# Needler_Rev_1_00.net
KiCad netlist of a schematic drawn in EAGLE
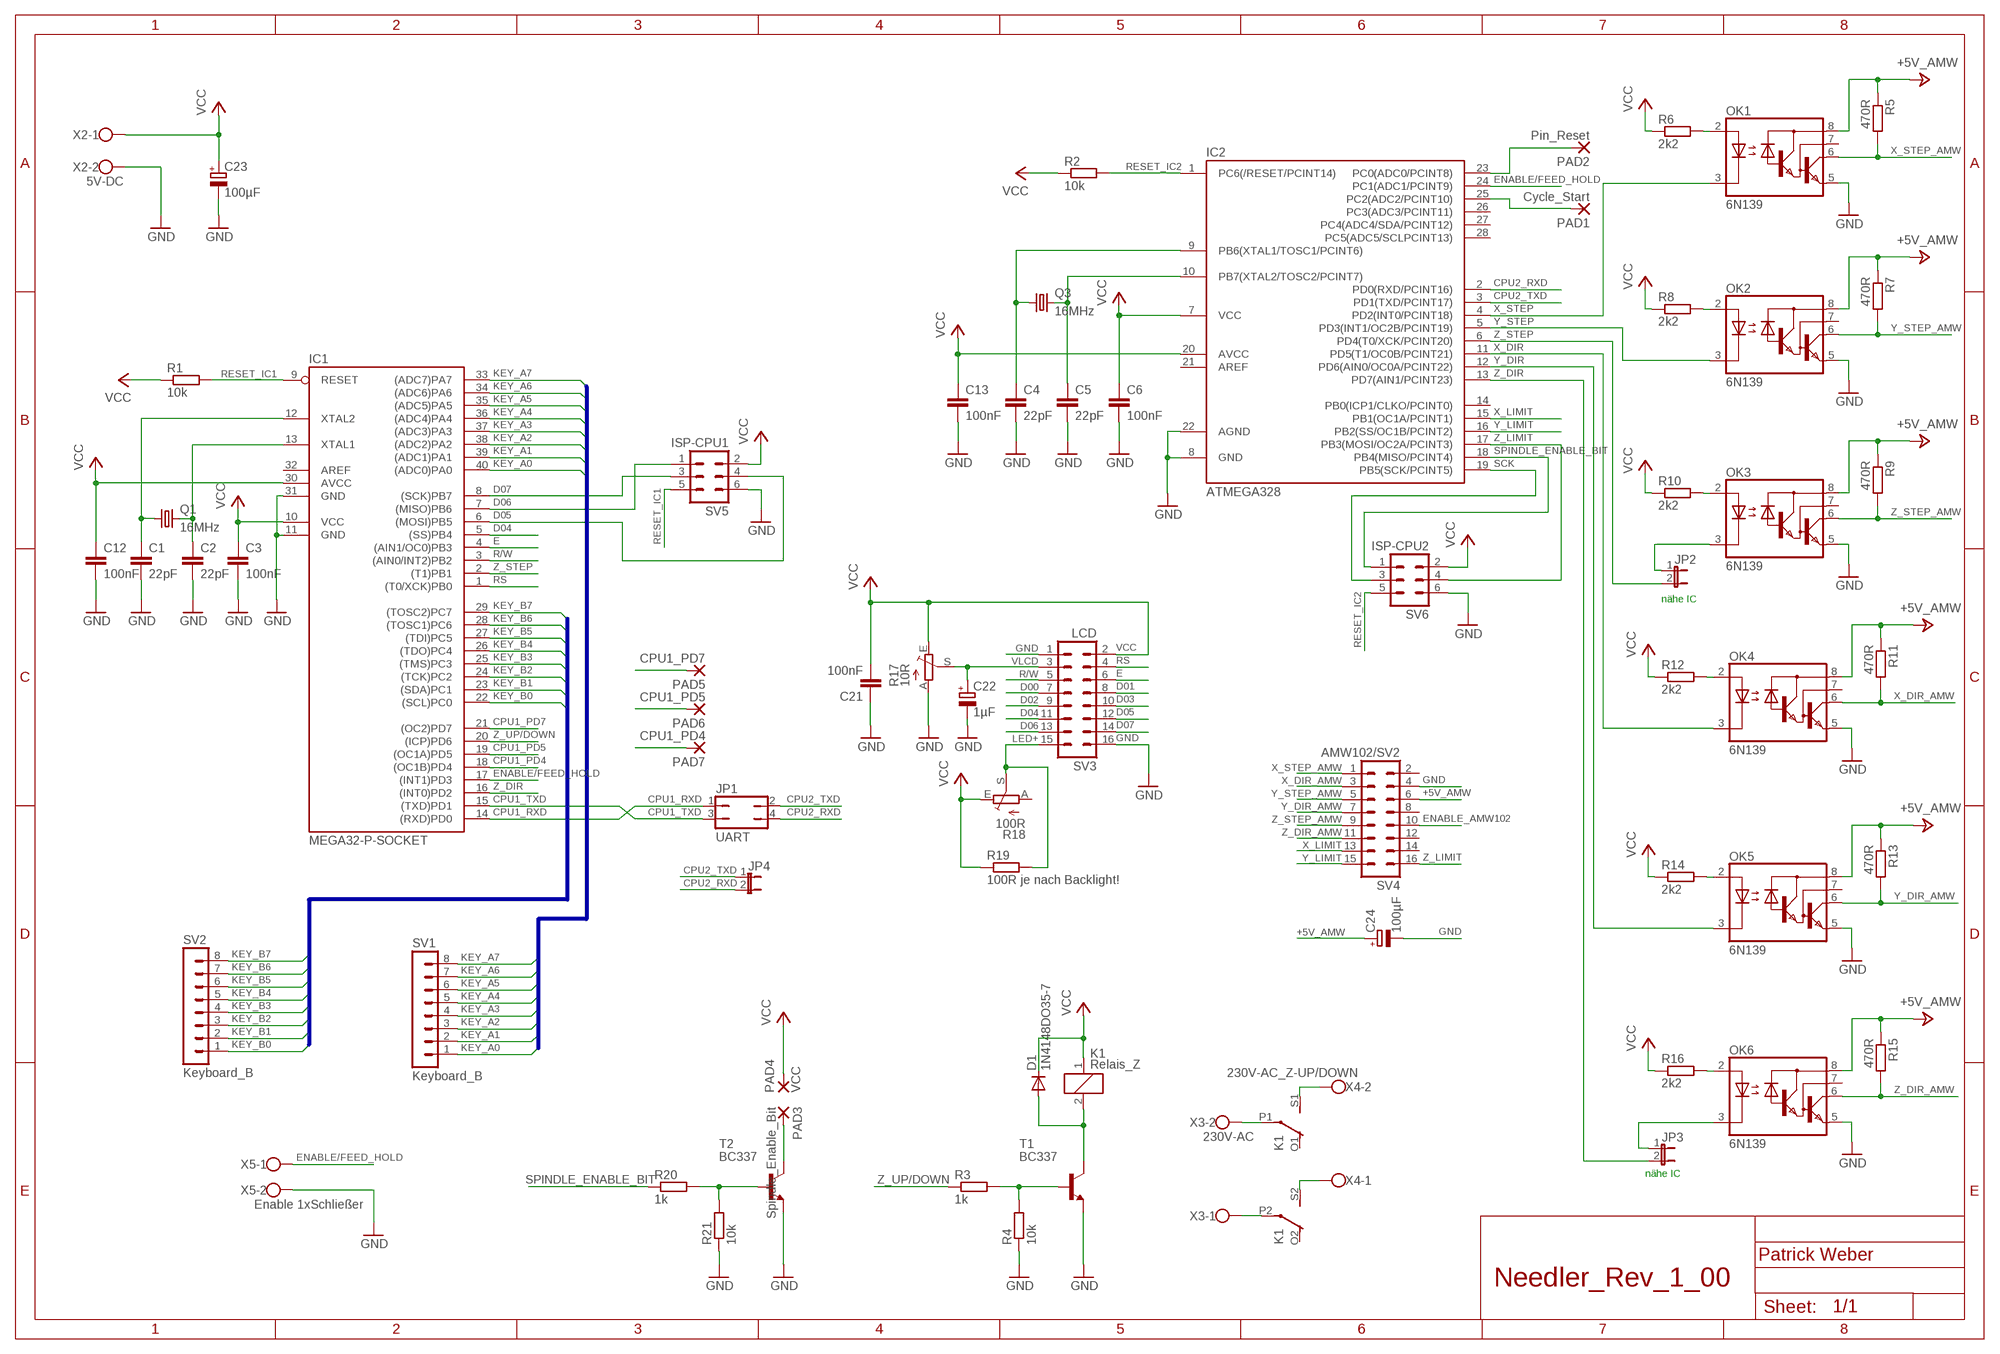
[diagram p0: schematic, sheet 1]

(export (version "E")
  (design (tool "Eeschema 10.0.6"))
  (components
    (comp (ref "C1")
      (value "22pF")
      (footprint "eagle-import:C1206")
      (libsource (lib "eagle-import") (part "C-EUC1206"))
    )
    (comp (ref "C2")
      (value "22pF")
      (footprint "eagle-import:C1206")
      (libsource (lib "eagle-import") (part "C-EUC1206"))
    )
    (comp (ref "C3")
      (value "100nF")
      (footprint "eagle-import:C050-024X044")
      (libsource (lib "eagle-import") (part "C-EU050-024X044"))
    )
    (comp (ref "C4")
      (value "22pF")
      (footprint "eagle-import:C1206")
      (libsource (lib "eagle-import") (part "C-EUC1206"))
    )
    (comp (ref "C5")
      (value "22pF")
      (footprint "eagle-import:C1206")
      (libsource (lib "eagle-import") (part "C-EUC1206"))
    )
    (comp (ref "C6")
      (value "100nF")
      (footprint "eagle-import:C050-024X044")
      (libsource (lib "eagle-import") (part "C-EU050-024X044"))
    )
    (comp (ref "C12")
      (value "100nF")
      (footprint "eagle-import:C050-024X044")
      (libsource (lib "eagle-import") (part "C-EU050-024X044"))
    )
    (comp (ref "C13")
      (value "100nF")
      (footprint "eagle-import:C050-024X044")
      (libsource (lib "eagle-import") (part "C-EU050-024X044"))
    )
    (comp (ref "C21")
      (value "100nF")
      (footprint "eagle-import:C050-024X044")
      (libsource (lib "eagle-import") (part "C-EU050-024X044"))
    )
    (comp (ref "C22")
      (value "1µF")
      (footprint "eagle-import:E2,5-6")
      (libsource (lib "eagle-import") (part "CPOL-EUE2.5-6"))
    )
    (comp (ref "C23")
      (value "100µF")
      (footprint "eagle-import:E2,5-6")
      (libsource (lib "eagle-import") (part "CPOL-EUE2.5-6"))
    )
    (comp (ref "C24")
      (value "100µF")
      (footprint "eagle-import:E2,5-6")
      (libsource (lib "eagle-import") (part "CPOL-EUE2.5-6"))
    )
    (comp (ref "D1")
      (value "1N4148DO35-7")
      (footprint "eagle-import:DO35-7")
      (libsource (lib "eagle-import") (part "1N4148DO35-7"))
    )
    (comp (ref "IC1")
      (value "MEGA32-P-SOCKET")
      (footprint "eagle-import:DIL40-SOCKET")
      (libsource (lib "eagle-import") (part "MEGA32-P-SOCKET"))
    )
    (comp (ref "IC2")
      (value "ATMEGA328")
      (footprint "eagle-import:DIL28-3")
      (libsource (lib "eagle-import") (part "MEGA48/88/168-PU"))
    )
    (comp (ref "JP1")
      (value "UART")
      (footprint "eagle-import:JP2Q")
      (libsource (lib "eagle-import") (part "JP2Q"))
    )
    (comp (ref "JP2")
      (value "JP1E")
      (footprint "eagle-import:JP1")
      (libsource (lib "eagle-import") (part "JP1E"))
    )
    (comp (ref "JP3")
      (value "JP1E")
      (footprint "eagle-import:JP1")
      (libsource (lib "eagle-import") (part "JP1E"))
    )
    (comp (ref "JP4")
      (value "JP1E")
      (footprint "eagle-import:JP1")
      (libsource (lib "eagle-import") (part "JP1E"))
    )
    (comp (ref "K1")
      (value "Relais_Z")
      (footprint "eagle-import:HF118F")
      (libsource (lib "eagle-import") (part "G2R2HF118F"))
    )
    (comp (ref "OK1")
      (value "6N139")
      (footprint "eagle-import:SO8-GW300")
      (libsource (lib "eagle-import") (part "6N138"))
    )
    (comp (ref "OK2")
      (value "6N139")
      (footprint "eagle-import:SO8-GW300")
      (libsource (lib "eagle-import") (part "6N138"))
    )
    (comp (ref "OK3")
      (value "6N139")
      (footprint "eagle-import:SO8-GW300")
      (libsource (lib "eagle-import") (part "6N138"))
    )
    (comp (ref "OK4")
      (value "6N139")
      (footprint "eagle-import:SO8-GW300")
      (libsource (lib "eagle-import") (part "6N138"))
    )
    (comp (ref "OK5")
      (value "6N139")
      (footprint "eagle-import:SO8-GW300")
      (libsource (lib "eagle-import") (part "6N138"))
    )
    (comp (ref "OK6")
      (value "6N139")
      (footprint "eagle-import:SO8-GW300")
      (libsource (lib "eagle-import") (part "6N138"))
    )
    (comp (ref "PAD1")
      (value "Cycle_Start")
      (footprint "eagle-import:2,54_1,1-2,54_5,08")
      (libsource (lib "eagle-import") (part "WIREPAD"))
    )
    (comp (ref "PAD2")
      (value "Pin_Reset")
      (footprint "eagle-import:2,54_1,1-2,54_5,08")
      (libsource (lib "eagle-import") (part "WIREPAD"))
    )
    (comp (ref "PAD3")
      (value "Spindle_Enable_Bit")
      (footprint "eagle-import:2,54_1,1-2,54_5,08")
      (libsource (lib "eagle-import") (part "WIREPAD"))
    )
    (comp (ref "PAD4")
      (value "VCC")
      (footprint "eagle-import:2,54_1,1-2,54_5,08")
      (libsource (lib "eagle-import") (part "2,54/1,1-1,54/5,08"))
    )
    (comp (ref "PAD5")
      (value "CPU1_PD7")
      (footprint "eagle-import:2,54_1,1-2,54_5,08")
      (libsource (lib "eagle-import") (part "WIREPAD"))
    )
    (comp (ref "PAD6")
      (value "CPU1_PD5")
      (footprint "eagle-import:2,54_1,1-2,54_5,08")
      (libsource (lib "eagle-import") (part "WIREPAD"))
    )
    (comp (ref "PAD7")
      (value "CPU1_PD4")
      (footprint "eagle-import:2,54_1,1-2,54_5,08")
      (libsource (lib "eagle-import") (part "WIREPAD"))
    )
    (comp (ref "Q1")
      (value "16MHz")
      (footprint "eagle-import:HC49U-V")
      (libsource (lib "eagle-import") (part "CRYSTALHC49U-V"))
    )
    (comp (ref "Q3")
      (value "16MHz")
      (footprint "eagle-import:HC49U-V")
      (libsource (lib "eagle-import") (part "CRYSTALHC49U-V"))
    )
    (comp (ref "R1")
      (value "10k")
      (footprint "eagle-import:0204_7")
      (libsource (lib "eagle-import") (part "R-EU_0204/7"))
    )
    (comp (ref "R2")
      (value "10k")
      (footprint "eagle-import:0204_7")
      (libsource (lib "eagle-import") (part "R-EU_0204/7"))
    )
    (comp (ref "R3")
      (value "1k")
      (footprint "eagle-import:0204_7")
      (libsource (lib "eagle-import") (part "R-EU_0204/7"))
    )
    (comp (ref "R4")
      (value "10k")
      (footprint "eagle-import:0204_7")
      (libsource (lib "eagle-import") (part "R-EU_0204/7"))
    )
    (comp (ref "R5")
      (value "470R")
      (footprint "eagle-import:0204_7")
      (libsource (lib "eagle-import") (part "R-EU_0204/7"))
    )
    (comp (ref "R6")
      (value "2k2")
      (footprint "eagle-import:0204_7")
      (libsource (lib "eagle-import") (part "R-EU_0204/7"))
    )
    (comp (ref "R7")
      (value "470R")
      (footprint "eagle-import:0204_7")
      (libsource (lib "eagle-import") (part "R-EU_0204/7"))
    )
    (comp (ref "R8")
      (value "2k2")
      (footprint "eagle-import:0204_7")
      (libsource (lib "eagle-import") (part "R-EU_0204/7"))
    )
    (comp (ref "R9")
      (value "470R")
      (footprint "eagle-import:0204_7")
      (libsource (lib "eagle-import") (part "R-EU_0204/7"))
    )
    (comp (ref "R10")
      (value "2k2")
      (footprint "eagle-import:0204_7")
      (libsource (lib "eagle-import") (part "R-EU_0204/7"))
    )
    (comp (ref "R11")
      (value "470R")
      (footprint "eagle-import:0204_7")
      (libsource (lib "eagle-import") (part "R-EU_0204/7"))
    )
    (comp (ref "R12")
      (value "2k2")
      (footprint "eagle-import:0204_7")
      (libsource (lib "eagle-import") (part "R-EU_0204/7"))
    )
    (comp (ref "R13")
      (value "470R")
      (footprint "eagle-import:0204_7")
      (libsource (lib "eagle-import") (part "R-EU_0204/7"))
    )
    (comp (ref "R14")
      (value "2k2")
      (footprint "eagle-import:0204_7")
      (libsource (lib "eagle-import") (part "R-EU_0204/7"))
    )
    (comp (ref "R15")
      (value "470R")
      (footprint "eagle-import:0204_7")
      (libsource (lib "eagle-import") (part "R-EU_0204/7"))
    )
    (comp (ref "R16")
      (value "2k2")
      (footprint "eagle-import:0204_7")
      (libsource (lib "eagle-import") (part "R-EU_0204/7"))
    )
    (comp (ref "R17")
      (value "10R")
      (footprint "eagle-import:CA6V")
      (libsource (lib "eagle-import") (part "TRIM_EU-CA6V"))
    )
    (comp (ref "R18")
      (value "100R")
      (footprint "eagle-import:CA6V")
      (libsource (lib "eagle-import") (part "TRIM_EU-CA6V"))
    )
    (comp (ref "R19")
      (value "100R je nach Backlight!")
      (footprint "eagle-import:0204_7")
      (libsource (lib "eagle-import") (part "R-EU_0204/7"))
    )
    (comp (ref "R20")
      (value "1k")
      (footprint "eagle-import:0204_7")
      (libsource (lib "eagle-import") (part "R-EU_0204/7"))
    )
    (comp (ref "R21")
      (value "10k")
      (footprint "eagle-import:0204_7")
      (libsource (lib "eagle-import") (part "R-EU_0204/7"))
    )
    (comp (ref "SV1")
      (value "Keyboard_B")
      (footprint "eagle-import:MA08-1")
      (libsource (lib "eagle-import") (part "MA08-1"))
    )
    (comp (ref "SV2")
      (value "Keyboard_B")
      (footprint "eagle-import:MA08-1")
      (libsource (lib "eagle-import") (part "MA08-1"))
    )
    (comp (ref "SV3")
      (value "LCD")
      (footprint "eagle-import:ML16")
      (libsource (lib "eagle-import") (part "ML16"))
    )
    (comp (ref "SV4")
      (value "AMW102/SV2")
      (footprint "eagle-import:ML16")
      (libsource (lib "eagle-import") (part "ML16"))
    )
    (comp (ref "SV5")
      (value "ISP-CPU1")
      (footprint "eagle-import:ML6")
      (libsource (lib "eagle-import") (part "ML6"))
    )
    (comp (ref "SV6")
      (value "ISP-CPU2")
      (footprint "eagle-import:ML6")
      (libsource (lib "eagle-import") (part "ML6"))
    )
    (comp (ref "T1")
      (value "BC337")
      (footprint "eagle-import:TO92")
      (libsource (lib "eagle-import") (part "BC337"))
    )
    (comp (ref "T2")
      (value "BC337")
      (footprint "eagle-import:TO92")
      (libsource (lib "eagle-import") (part "BC337"))
    )
    (comp (ref "X2")
      (value "5V-DC")
      (footprint "eagle-import:W237-102")
      (fields (field (name "MPN") "237-102"))
      (libsource (lib "eagle-import") (part "W237-102"))
    )
    (comp (ref "X3")
      (value "230V-AC")
      (footprint "eagle-import:W237-102")
      (fields (field (name "MPN") "237-102"))
      (libsource (lib "eagle-import") (part "W237-102"))
    )
    (comp (ref "X4")
      (value "230V-AC_Z-UP/DOWN")
      (footprint "eagle-import:W237-102")
      (fields (field (name "MPN") "237-102"))
      (libsource (lib "eagle-import") (part "W237-102"))
    )
    (comp (ref "X5")
      (value "Enable 1xSchließer")
      (footprint "eagle-import:W237-102")
      (fields (field (name "MPN") "237-102"))
      (libsource (lib "eagle-import") (part "W237-102"))
    )
  )
  (nets
    (net (code "1") (name "+5V_AMW") (class "Default")
      (node (ref "C24") (pin "+") (pinfunction "+_+") (pintype "passive"))
      (node (ref "OK1") (pin "8") (pinfunction "VCC_8") (pintype "passive"))
      (node (ref "OK2") (pin "8") (pinfunction "VCC_8") (pintype "passive"))
      (node (ref "OK3") (pin "8") (pinfunction "VCC_8") (pintype "passive"))
      (node (ref "OK4") (pin "8") (pinfunction "VCC_8") (pintype "passive"))
      (node (ref "OK5") (pin "8") (pinfunction "VCC_8") (pintype "passive"))
      (node (ref "OK6") (pin "8") (pinfunction "VCC_8") (pintype "passive"))
      (node (ref "R11") (pin "1") (pinfunction "1_1") (pintype "passive"))
      (node (ref "R13") (pin "1") (pinfunction "1_1") (pintype "passive"))
      (node (ref "R15") (pin "1") (pinfunction "1_1") (pintype "passive"))
      (node (ref "R5") (pin "1") (pinfunction "1_1") (pintype "passive"))
      (node (ref "R7") (pin "1") (pinfunction "1_1") (pintype "passive"))
      (node (ref "R9") (pin "1") (pinfunction "1_1") (pintype "passive"))
      (node (ref "SV4") (pin "6") (pinfunction "6_6") (pintype "passive"))
    )
    (net (code "2") (name "/CPU1_PD4") (class "Default")
      (node (ref "IC1") (pin "18") (pinfunction "(OC1B)PD4_18") (pintype "bidirectional"))
      (node (ref "PAD7") (pin "1") (pinfunction "P_1") (pintype "passive"))
    )
    (net (code "3") (name "/CPU1_PD5") (class "Default")
      (node (ref "IC1") (pin "19") (pinfunction "(OC1A)PD5_19") (pintype "bidirectional"))
      (node (ref "PAD6") (pin "1") (pinfunction "P_1") (pintype "passive"))
    )
    (net (code "4") (name "/CPU1_PD7") (class "Default")
      (node (ref "IC1") (pin "21") (pinfunction "(OC2)PD7_21") (pintype "bidirectional"))
      (node (ref "PAD5") (pin "1") (pinfunction "P_1") (pintype "passive"))
    )
    (net (code "5") (name "/CPU1_RXD") (class "Default")
      (node (ref "IC1") (pin "14") (pinfunction "(RXD)PD0_14") (pintype "bidirectional"))
      (node (ref "JP1") (pin "1") (pinfunction "1_1") (pintype "passive"))
    )
    (net (code "6") (name "/CPU1_TXD") (class "Default")
      (node (ref "IC1") (pin "15") (pinfunction "(TXD)PD1_15") (pintype "bidirectional"))
      (node (ref "JP1") (pin "3") (pinfunction "3_3") (pintype "passive"))
    )
    (net (code "7") (name "/CPU2_RXD") (class "Default")
      (node (ref "IC2") (pin "2") (pinfunction "PD0(RXD/PCINT16)_2") (pintype "bidirectional"))
      (node (ref "JP1") (pin "4") (pinfunction "4_4") (pintype "passive"))
      (node (ref "JP4") (pin "2") (pinfunction "2_2") (pintype "passive"))
    )
    (net (code "8") (name "/CPU2_TXD") (class "Default")
      (node (ref "IC2") (pin "3") (pinfunction "PD1(TXD/PCINT17)_3") (pintype "bidirectional"))
      (node (ref "JP1") (pin "2") (pinfunction "2_2") (pintype "passive"))
      (node (ref "JP4") (pin "1") (pinfunction "1_1") (pintype "passive"))
    )
    (net (code "9") (name "/D00") (class "Default")
      (node (ref "SV3") (pin "7") (pinfunction "7_7") (pintype "passive"))
    )
    (net (code "10") (name "/D01") (class "Default")
      (node (ref "SV3") (pin "8") (pinfunction "8_8") (pintype "passive"))
    )
    (net (code "11") (name "/D02") (class "Default")
      (node (ref "SV3") (pin "9") (pinfunction "9_9") (pintype "passive"))
    )
    (net (code "12") (name "/D03") (class "Default")
      (node (ref "SV3") (pin "10") (pinfunction "10_10") (pintype "passive"))
    )
    (net (code "13") (name "/D04") (class "Default")
      (node (ref "IC1") (pin "5") (pinfunction "(SS)PB4_5") (pintype "bidirectional"))
      (node (ref "SV3") (pin "11") (pinfunction "11_11") (pintype "passive"))
    )
    (net (code "14") (name "/D05") (class "Default")
      (node (ref "IC1") (pin "6") (pinfunction "(MOSI)PB5_6") (pintype "bidirectional"))
      (node (ref "SV3") (pin "12") (pinfunction "12_12") (pintype "passive"))
      (node (ref "SV5") (pin "4") (pinfunction "4_4") (pintype "passive"))
    )
    (net (code "15") (name "/D06") (class "Default")
      (node (ref "IC1") (pin "7") (pinfunction "(MISO)PB6_7") (pintype "bidirectional"))
      (node (ref "SV3") (pin "13") (pinfunction "13_13") (pintype "passive"))
      (node (ref "SV5") (pin "1") (pinfunction "1_1") (pintype "passive"))
    )
    (net (code "16") (name "/D07") (class "Default")
      (node (ref "IC1") (pin "8") (pinfunction "(SCK)PB7_8") (pintype "bidirectional"))
      (node (ref "SV3") (pin "14") (pinfunction "14_14") (pintype "passive"))
      (node (ref "SV5") (pin "3") (pinfunction "3_3") (pintype "passive"))
    )
    (net (code "17") (name "/E") (class "Default")
      (node (ref "IC1") (pin "4") (pinfunction "(AIN1/OC0)PB3_4") (pintype "bidirectional"))
      (node (ref "SV3") (pin "6") (pinfunction "6_6") (pintype "passive"))
    )
    (net (code "18") (name "/ENABLE_AMW102") (class "Default")
      (node (ref "SV4") (pin "10") (pinfunction "10_10") (pintype "passive"))
    )
    (net (code "19") (name "/ENABLE{slash}FEED_HOLD") (class "Default")
      (node (ref "IC1") (pin "17") (pinfunction "(INT1)PD3_17") (pintype "bidirectional"))
      (node (ref "IC2") (pin "24") (pinfunction "PC1(ADC1/PCINT9)_24") (pintype "bidirectional"))
      (node (ref "X5") (pin "1") (pinfunction "KL_1") (pintype "passive"))
    )
    (net (code "20") (name "/KEY_A0") (class "Default")
      (node (ref "IC1") (pin "40") (pinfunction "(ADC0)PA0_40") (pintype "bidirectional"))
      (node (ref "SV1") (pin "1") (pinfunction "1_1") (pintype "passive"))
    )
    (net (code "21") (name "/KEY_A1") (class "Default")
      (node (ref "IC1") (pin "39") (pinfunction "(ADC1)PA1_39") (pintype "bidirectional"))
      (node (ref "SV1") (pin "2") (pinfunction "2_2") (pintype "passive"))
    )
    (net (code "22") (name "/KEY_A2") (class "Default")
      (node (ref "IC1") (pin "38") (pinfunction "(ADC2)PA2_38") (pintype "bidirectional"))
      (node (ref "SV1") (pin "3") (pinfunction "3_3") (pintype "passive"))
    )
    (net (code "23") (name "/KEY_A3") (class "Default")
      (node (ref "IC1") (pin "37") (pinfunction "(ADC3)PA3_37") (pintype "bidirectional"))
      (node (ref "SV1") (pin "4") (pinfunction "4_4") (pintype "passive"))
    )
    (net (code "24") (name "/KEY_A4") (class "Default")
      (node (ref "IC1") (pin "36") (pinfunction "(ADC4)PA4_36") (pintype "bidirectional"))
      (node (ref "SV1") (pin "5") (pinfunction "5_5") (pintype "passive"))
    )
    (net (code "25") (name "/KEY_A5") (class "Default")
      (node (ref "IC1") (pin "35") (pinfunction "(ADC5)PA5_35") (pintype "bidirectional"))
      (node (ref "SV1") (pin "6") (pinfunction "6_6") (pintype "passive"))
    )
    (net (code "26") (name "/KEY_A6") (class "Default")
      (node (ref "IC1") (pin "34") (pinfunction "(ADC6)PA6_34") (pintype "bidirectional"))
      (node (ref "SV1") (pin "7") (pinfunction "7_7") (pintype "passive"))
    )
    (net (code "27") (name "/KEY_A7") (class "Default")
      (node (ref "IC1") (pin "33") (pinfunction "(ADC7)PA7_33") (pintype "bidirectional"))
      (node (ref "SV1") (pin "8") (pinfunction "8_8") (pintype "passive"))
    )
    (net (code "28") (name "/KEY_B0") (class "Default")
      (node (ref "IC1") (pin "22") (pinfunction "(SCL)PC0_22") (pintype "bidirectional"))
      (node (ref "SV2") (pin "1") (pinfunction "1_1") (pintype "passive"))
    )
    (net (code "29") (name "/KEY_B1") (class "Default")
      (node (ref "IC1") (pin "23") (pinfunction "(SDA)PC1_23") (pintype "bidirectional"))
      (node (ref "SV2") (pin "2") (pinfunction "2_2") (pintype "passive"))
    )
    (net (code "30") (name "/KEY_B2") (class "Default")
      (node (ref "IC1") (pin "24") (pinfunction "(TCK)PC2_24") (pintype "bidirectional"))
      (node (ref "SV2") (pin "3") (pinfunction "3_3") (pintype "passive"))
    )
    (net (code "31") (name "/KEY_B3") (class "Default")
      (node (ref "IC1") (pin "25") (pinfunction "(TMS)PC3_25") (pintype "bidirectional"))
      (node (ref "SV2") (pin "4") (pinfunction "4_4") (pintype "passive"))
    )
    (net (code "32") (name "/KEY_B4") (class "Default")
      (node (ref "IC1") (pin "26") (pinfunction "(TDO)PC4_26") (pintype "bidirectional"))
      (node (ref "SV2") (pin "5") (pinfunction "5_5") (pintype "passive"))
    )
    (net (code "33") (name "/KEY_B5") (class "Default")
      (node (ref "IC1") (pin "27") (pinfunction "(TDI)PC5_27") (pintype "bidirectional"))
      (node (ref "SV2") (pin "6") (pinfunction "6_6") (pintype "passive"))
    )
    (net (code "34") (name "/KEY_B6") (class "Default")
      (node (ref "IC1") (pin "28") (pinfunction "(TOSC1)PC6_28") (pintype "bidirectional"))
      (node (ref "SV2") (pin "7") (pinfunction "7_7") (pintype "passive"))
    )
    (net (code "35") (name "/KEY_B7") (class "Default")
      (node (ref "IC1") (pin "29") (pinfunction "(TOSC2)PC7_29") (pintype "bidirectional"))
      (node (ref "SV2") (pin "8") (pinfunction "8_8") (pintype "passive"))
    )
    (net (code "36") (name "/LED+") (class "Default")
      (node (ref "R18") (pin "S") (pinfunction "S_S") (pintype "passive"))
      (node (ref "R19") (pin "2") (pinfunction "2_2") (pintype "passive"))
      (node (ref "SV3") (pin "15") (pinfunction "15_15") (pintype "passive"))
    )
    (net (code "37") (name "/RESET_IC1") (class "Default")
      (node (ref "IC1") (pin "9") (pinfunction "RESET_9") (pintype "input"))
      (node (ref "R1") (pin "2") (pinfunction "2_2") (pintype "passive"))
      (node (ref "SV5") (pin "5") (pinfunction "5_5") (pintype "passive"))
    )
    (net (code "38") (name "/RESET_IC2") (class "Default")
      (node (ref "IC2") (pin "1") (pinfunction "PC6(/RESET/PCINT14)_1") (pintype "bidirectional"))
      (node (ref "R2") (pin "2") (pinfunction "2_2") (pintype "passive"))
      (node (ref "SV6") (pin "5") (pinfunction "5_5") (pintype "passive"))
    )
    (net (code "39") (name "/RS") (class "Default")
      (node (ref "IC1") (pin "1") (pinfunction "(T0/XCK)PB0_1") (pintype "bidirectional"))
      (node (ref "SV3") (pin "4") (pinfunction "4_4") (pintype "passive"))
    )
    (net (code "40") (name "/R{slash}W") (class "Default")
      (node (ref "IC1") (pin "3") (pinfunction "(AIN0/INT2)PB2_3") (pintype "bidirectional"))
      (node (ref "SV3") (pin "5") (pinfunction "5_5") (pintype "passive"))
    )
    (net (code "41") (name "/SCK") (class "Default")
      (node (ref "IC2") (pin "19") (pinfunction "PB5(SCK/PCINT5)_19") (pintype "bidirectional"))
      (node (ref "SV6") (pin "3") (pinfunction "3_3") (pintype "passive"))
    )
    (net (code "42") (name "/SPINDLE_ENABLE_BIT") (class "Default")
      (node (ref "IC2") (pin "18") (pinfunction "PB4(MISO/PCINT4)_18") (pintype "bidirectional"))
      (node (ref "R20") (pin "1") (pinfunction "1_1") (pintype "passive"))
      (node (ref "SV6") (pin "1") (pinfunction "1_1") (pintype "passive"))
    )
    (net (code "43") (name "/VLCD") (class "Default")
      (node (ref "C22") (pin "+") (pinfunction "+_+") (pintype "passive"))
      (node (ref "R17") (pin "S") (pinfunction "S_S") (pintype "passive"))
      (node (ref "SV3") (pin "3") (pinfunction "3_3") (pintype "passive"))
    )
    (net (code "44") (name "/X_DIR") (class "Default")
      (node (ref "IC2") (pin "11") (pinfunction "PD5(T1/OC0B/PCINT21)_11") (pintype "bidirectional"))
      (node (ref "OK4") (pin "3") (pinfunction "C_3") (pintype "passive"))
    )
    (net (code "45") (name "/X_DIR_AMW") (class "Default")
      (node (ref "OK4") (pin "6") (pinfunction "VO_6") (pintype "passive"))
      (node (ref "R11") (pin "2") (pinfunction "2_2") (pintype "passive"))
      (node (ref "SV4") (pin "3") (pinfunction "3_3") (pintype "passive"))
    )
    (net (code "46") (name "/X_LIMIT") (class "Default")
      (node (ref "IC2") (pin "15") (pinfunction "PB1(OC1A/PCINT1)_15") (pintype "bidirectional"))
      (node (ref "SV4") (pin "13") (pinfunction "13_13") (pintype "passive"))
    )
    (net (code "47") (name "/X_STEP") (class "Default")
      (node (ref "IC2") (pin "4") (pinfunction "PD2(INT0/PCINT18)_4") (pintype "bidirectional"))
      (node (ref "OK1") (pin "3") (pinfunction "C_3") (pintype "passive"))
    )
    (net (code "48") (name "/X_STEP_AMW") (class "Default")
      (node (ref "OK1") (pin "6") (pinfunction "VO_6") (pintype "passive"))
      (node (ref "R5") (pin "2") (pinfunction "2_2") (pintype "passive"))
      (node (ref "SV4") (pin "1") (pinfunction "1_1") (pintype "passive"))
    )
    (net (code "49") (name "/Y_DIR") (class "Default")
      (node (ref "IC2") (pin "12") (pinfunction "PD6(AIN0/OC0A/PCINT22)_12") (pintype "bidirectional"))
      (node (ref "OK5") (pin "3") (pinfunction "C_3") (pintype "passive"))
    )
    (net (code "50") (name "/Y_DIR_AMW") (class "Default")
      (node (ref "OK5") (pin "6") (pinfunction "VO_6") (pintype "passive"))
      (node (ref "R13") (pin "2") (pinfunction "2_2") (pintype "passive"))
      (node (ref "SV4") (pin "7") (pinfunction "7_7") (pintype "passive"))
    )
    (net (code "51") (name "/Y_LIMIT") (class "Default")
      (node (ref "IC2") (pin "16") (pinfunction "PB2(SS/OC1B/PCINT2)_16") (pintype "bidirectional"))
      (node (ref "SV4") (pin "15") (pinfunction "15_15") (pintype "passive"))
    )
    (net (code "52") (name "/Y_STEP") (class "Default")
      (node (ref "IC2") (pin "5") (pinfunction "PD3(INT1/OC2B/PCINT19)_5") (pintype "bidirectional"))
      (node (ref "OK2") (pin "3") (pinfunction "C_3") (pintype "passive"))
    )
    (net (code "53") (name "/Y_STEP_AMW") (class "Default")
      (node (ref "OK2") (pin "6") (pinfunction "VO_6") (pintype "passive"))
      (node (ref "R7") (pin "2") (pinfunction "2_2") (pintype "passive"))
      (node (ref "SV4") (pin "5") (pinfunction "5_5") (pintype "passive"))
    )
    (net (code "54") (name "/Z_DIR") (class "Default")
      (node (ref "IC1") (pin "16") (pinfunction "(INT0)PD2_16") (pintype "bidirectional"))
      (node (ref "IC2") (pin "13") (pinfunction "PD7(AIN1/PCINT23)_13") (pintype "bidirectional"))
      (node (ref "JP3") (pin "2") (pinfunction "2_2") (pintype "passive"))
    )
    (net (code "55") (name "/Z_DIR_AMW") (class "Default")
      (node (ref "OK6") (pin "6") (pinfunction "VO_6") (pintype "passive"))
      (node (ref "R15") (pin "2") (pinfunction "2_2") (pintype "passive"))
      (node (ref "SV4") (pin "11") (pinfunction "11_11") (pintype "passive"))
    )
    (net (code "56") (name "/Z_LIMIT") (class "Default")
      (node (ref "IC2") (pin "17") (pinfunction "PB3(MOSI/OC2A/PCINT3)_17") (pintype "bidirectional"))
      (node (ref "SV4") (pin "16") (pinfunction "16_16") (pintype "passive"))
      (node (ref "SV6") (pin "4") (pinfunction "4_4") (pintype "passive"))
    )
    (net (code "57") (name "/Z_STEP") (class "Default")
      (node (ref "IC1") (pin "2") (pinfunction "(T1)PB1_2") (pintype "bidirectional"))
      (node (ref "IC2") (pin "6") (pinfunction "PD4(T0/XCK/PCINT20)_6") (pintype "bidirectional"))
      (node (ref "JP2") (pin "2") (pinfunction "2_2") (pintype "passive"))
    )
    (net (code "58") (name "/Z_STEP_AMW") (class "Default")
      (node (ref "OK3") (pin "6") (pinfunction "VO_6") (pintype "passive"))
      (node (ref "R9") (pin "2") (pinfunction "2_2") (pintype "passive"))
      (node (ref "SV4") (pin "9") (pinfunction "9_9") (pintype "passive"))
    )
    (net (code "59") (name "/Z_UP{slash}DOWN") (class "Default")
      (node (ref "IC1") (pin "20") (pinfunction "(ICP)PD6_20") (pintype "bidirectional"))
      (node (ref "R3") (pin "1") (pinfunction "1_1") (pintype "passive"))
    )
    (net (code "60") (name "GND") (class "Default")
      (node (ref "C1") (pin "2") (pinfunction "2_2") (pintype "passive"))
      (node (ref "C12") (pin "2") (pinfunction "2_2") (pintype "passive"))
      (node (ref "C13") (pin "2") (pinfunction "2_2") (pintype "passive"))
      (node (ref "C2") (pin "2") (pinfunction "2_2") (pintype "passive"))
      (node (ref "C21") (pin "1") (pinfunction "1_1") (pintype "passive"))
      (node (ref "C22") (pin "-") (pinfunction "-_-") (pintype "passive"))
      (node (ref "C23") (pin "-") (pinfunction "-_-") (pintype "passive"))
      (node (ref "C24") (pin "-") (pinfunction "-_-") (pintype "passive"))
      (node (ref "C3") (pin "2") (pinfunction "2_2") (pintype "passive"))
      (node (ref "C4") (pin "2") (pinfunction "2_2") (pintype "passive"))
      (node (ref "C5") (pin "2") (pinfunction "2_2") (pintype "passive"))
      (node (ref "C6") (pin "2") (pinfunction "2_2") (pintype "passive"))
      (node (ref "IC1") (pin "11") (pinfunction "GND_11") (pintype "power_in"))
      (node (ref "IC1") (pin "31") (pinfunction "GND_31") (pintype "power_in"))
      (node (ref "IC2") (pin "22") (pinfunction "AGND_22") (pintype "power_in"))
      (node (ref "IC2") (pin "8") (pinfunction "GND_8") (pintype "power_in"))
      (node (ref "OK1") (pin "5") (pinfunction "GND_5") (pintype "passive"))
      (node (ref "OK2") (pin "5") (pinfunction "GND_5") (pintype "passive"))
      (node (ref "OK3") (pin "5") (pinfunction "GND_5") (pintype "passive"))
      (node (ref "OK4") (pin "5") (pinfunction "GND_5") (pintype "passive"))
      (node (ref "OK5") (pin "5") (pinfunction "GND_5") (pintype "passive"))
      (node (ref "OK6") (pin "5") (pinfunction "GND_5") (pintype "passive"))
      (node (ref "R17") (pin "A") (pinfunction "A_A") (pintype "passive"))
      (node (ref "R21") (pin "1") (pinfunction "1_1") (pintype "passive"))
      (node (ref "R4") (pin "1") (pinfunction "1_1") (pintype "passive"))
      (node (ref "SV3") (pin "1") (pinfunction "1_1") (pintype "passive"))
      (node (ref "SV3") (pin "16") (pinfunction "16_16") (pintype "passive"))
      (node (ref "SV4") (pin "4") (pinfunction "4_4") (pintype "passive"))
      (node (ref "SV5") (pin "6") (pinfunction "6_6") (pintype "passive"))
      (node (ref "SV6") (pin "6") (pinfunction "6_6") (pintype "passive"))
      (node (ref "T1") (pin "1") (pinfunction "E_1") (pintype "passive"))
      (node (ref "T2") (pin "1") (pinfunction "E_1") (pintype "passive"))
      (node (ref "X2") (pin "2") (pinfunction "KL_2") (pintype "passive"))
      (node (ref "X5") (pin "2") (pinfunction "KL_2") (pintype "passive"))
    )
    (net (code "61") (name "Net-(IC1-XTAL1)") (class "Default")
      (node (ref "C2") (pin "1") (pinfunction "1_1") (pintype "passive"))
      (node (ref "IC1") (pin "13") (pinfunction "XTAL1_13") (pintype "bidirectional"))
      (node (ref "Q1") (pin "2") (pinfunction "2_2") (pintype "passive"))
    )
    (net (code "62") (name "Net-(IC1-XTAL2)") (class "Default")
      (node (ref "C1") (pin "1") (pinfunction "1_1") (pintype "passive"))
      (node (ref "IC1") (pin "12") (pinfunction "XTAL2_12") (pintype "bidirectional"))
      (node (ref "Q1") (pin "1") (pinfunction "1_1") (pintype "passive"))
    )
    (net (code "63") (name "Net-(IC2-PB6(XTAL1{slash}TOSC1{slash}PCINT6))") (class "Default")
      (node (ref "C4") (pin "1") (pinfunction "1_1") (pintype "passive"))
      (node (ref "IC2") (pin "9") (pinfunction "PB6(XTAL1/TOSC1/PCINT6)_9") (pintype "bidirectional"))
      (node (ref "Q3") (pin "1") (pinfunction "1_1") (pintype "passive"))
    )
    (net (code "64") (name "Net-(IC2-PB7(XTAL2{slash}TOSC2{slash}PCINT7))") (class "Default")
      (node (ref "C5") (pin "1") (pinfunction "1_1") (pintype "passive"))
      (node (ref "IC2") (pin "10") (pinfunction "PB7(XTAL2/TOSC2/PCINT7)_10") (pintype "bidirectional"))
      (node (ref "Q3") (pin "2") (pinfunction "2_2") (pintype "passive"))
    )
    (net (code "65") (name "Net-(IC2-PC0(ADC0{slash}PCINT8))") (class "Default")
      (node (ref "IC2") (pin "23") (pinfunction "PC0(ADC0/PCINT8)_23") (pintype "bidirectional"))
      (node (ref "PAD2") (pin "1") (pinfunction "P_1") (pintype "passive"))
    )
    (net (code "66") (name "Net-(IC2-PC2(ADC2{slash}PCINT10))") (class "Default")
      (node (ref "IC2") (pin "25") (pinfunction "PC2(ADC2/PCINT10)_25") (pintype "bidirectional"))
      (node (ref "PAD1") (pin "1") (pinfunction "P_1") (pintype "passive"))
    )
    (net (code "67") (name "Net-(K1B-P)") (class "Default")
      (node (ref "K1") (pin "P1") (pinfunction "P_P1") (pintype "passive"))
      (node (ref "X3") (pin "2") (pinfunction "KL_2") (pintype "passive"))
    )
    (net (code "68") (name "Net-(K1B-S)") (class "Default")
      (node (ref "K1") (pin "S1") (pinfunction "S_S1") (pintype "passive"))
      (node (ref "X4") (pin "2") (pinfunction "KL_2") (pintype "passive"))
    )
    (net (code "69") (name "Net-(K1C-P)") (class "Default")
      (node (ref "K1") (pin "P2") (pinfunction "P_P2") (pintype "passive"))
      (node (ref "X3") (pin "1") (pinfunction "KL_1") (pintype "passive"))
    )
    (net (code "70") (name "Net-(K1C-S)") (class "Default")
      (node (ref "K1") (pin "S2") (pinfunction "S_S2") (pintype "passive"))
      (node (ref "X4") (pin "1") (pinfunction "KL_1") (pintype "passive"))
    )
    (net (code "71") (name "Net-(OK1-A)") (class "Default")
      (node (ref "OK1") (pin "2") (pinfunction "A_2") (pintype "passive"))
      (node (ref "R6") (pin "2") (pinfunction "2_2") (pintype "passive"))
    )
    (net (code "72") (name "Net-(OK2-A)") (class "Default")
      (node (ref "OK2") (pin "2") (pinfunction "A_2") (pintype "passive"))
      (node (ref "R8") (pin "2") (pinfunction "2_2") (pintype "passive"))
    )
    (net (code "73") (name "Net-(OK3-A)") (class "Default")
      (node (ref "OK3") (pin "2") (pinfunction "A_2") (pintype "passive"))
      (node (ref "R10") (pin "2") (pinfunction "2_2") (pintype "passive"))
    )
    (net (code "74") (name "Net-(OK3-C)") (class "Default")
      (node (ref "JP2") (pin "1") (pinfunction "1_1") (pintype "passive"))
      (node (ref "OK3") (pin "3") (pinfunction "C_3") (pintype "passive"))
    )
    (net (code "75") (name "Net-(OK4-A)") (class "Default")
      (node (ref "OK4") (pin "2") (pinfunction "A_2") (pintype "passive"))
      (node (ref "R12") (pin "2") (pinfunction "2_2") (pintype "passive"))
    )
    (net (code "76") (name "Net-(OK5-A)") (class "Default")
      (node (ref "OK5") (pin "2") (pinfunction "A_2") (pintype "passive"))
      (node (ref "R14") (pin "2") (pinfunction "2_2") (pintype "passive"))
    )
    (net (code "77") (name "Net-(OK6-A)") (class "Default")
      (node (ref "OK6") (pin "2") (pinfunction "A_2") (pintype "passive"))
      (node (ref "R16") (pin "2") (pinfunction "2_2") (pintype "passive"))
    )
    (net (code "78") (name "Net-(OK6-C)") (class "Default")
      (node (ref "JP3") (pin "1") (pinfunction "1_1") (pintype "passive"))
      (node (ref "OK6") (pin "3") (pinfunction "C_3") (pintype "passive"))
    )
    (net (code "79") (name "Net-(PAD3-P)") (class "Default")
      (node (ref "PAD3") (pin "1") (pinfunction "P_1") (pintype "passive"))
      (node (ref "T2") (pin "3") (pinfunction "C_3") (pintype "passive"))
    )
    (net (code "80") (name "Net-(T1-B)") (class "Default")
      (node (ref "R3") (pin "2") (pinfunction "2_2") (pintype "passive"))
      (node (ref "R4") (pin "2") (pinfunction "2_2") (pintype "passive"))
      (node (ref "T1") (pin "2") (pinfunction "B_2") (pintype "passive"))
    )
    (net (code "81") (name "Net-(T1-C)") (class "Default")
      (node (ref "D1") (pin "A") (pinfunction "A_A") (pintype "passive"))
      (node (ref "K1") (pin "2") (pinfunction "2_2") (pintype "passive"))
      (node (ref "T1") (pin "3") (pinfunction "C_3") (pintype "passive"))
    )
    (net (code "82") (name "Net-(T2-B)") (class "Default")
      (node (ref "R20") (pin "2") (pinfunction "2_2") (pintype "passive"))
      (node (ref "R21") (pin "2") (pinfunction "2_2") (pintype "passive"))
      (node (ref "T2") (pin "2") (pinfunction "B_2") (pintype "passive"))
    )
    (net (code "83") (name "VCC") (class "Default")
      (node (ref "C12") (pin "1") (pinfunction "1_1") (pintype "passive"))
      (node (ref "C13") (pin "1") (pinfunction "1_1") (pintype "passive"))
      (node (ref "C21") (pin "2") (pinfunction "2_2") (pintype "passive"))
      (node (ref "C23") (pin "+") (pinfunction "+_+") (pintype "passive"))
      (node (ref "C3") (pin "1") (pinfunction "1_1") (pintype "passive"))
      (node (ref "C6") (pin "1") (pinfunction "1_1") (pintype "passive"))
      (node (ref "D1") (pin "C") (pinfunction "C_C") (pintype "passive"))
      (node (ref "IC1") (pin "10") (pinfunction "VCC_10") (pintype "power_in"))
      (node (ref "IC1") (pin "30") (pinfunction "AVCC_30") (pintype "power_in"))
      (node (ref "IC2") (pin "20") (pinfunction "AVCC_20") (pintype "passive"))
      (node (ref "IC2") (pin "7") (pinfunction "VCC_7") (pintype "power_in"))
      (node (ref "K1") (pin "1") (pinfunction "1_1") (pintype "passive"))
      (node (ref "PAD4") (pin "1") (pinfunction "P_1") (pintype "passive"))
      (node (ref "R1") (pin "1") (pinfunction "1_1") (pintype "passive"))
      (node (ref "R10") (pin "1") (pinfunction "1_1") (pintype "passive"))
      (node (ref "R12") (pin "1") (pinfunction "1_1") (pintype "passive"))
      (node (ref "R14") (pin "1") (pinfunction "1_1") (pintype "passive"))
      (node (ref "R16") (pin "1") (pinfunction "1_1") (pintype "passive"))
      (node (ref "R17") (pin "E") (pinfunction "E_E") (pintype "passive"))
      (node (ref "R18") (pin "E") (pinfunction "E_E") (pintype "passive"))
      (node (ref "R19") (pin "1") (pinfunction "1_1") (pintype "passive"))
      (node (ref "R2") (pin "1") (pinfunction "1_1") (pintype "passive"))
      (node (ref "R6") (pin "1") (pinfunction "1_1") (pintype "passive"))
      (node (ref "R8") (pin "1") (pinfunction "1_1") (pintype "passive"))
      (node (ref "SV3") (pin "2") (pinfunction "2_2") (pintype "passive"))
      (node (ref "SV5") (pin "2") (pinfunction "2_2") (pintype "passive"))
      (node (ref "SV6") (pin "2") (pinfunction "2_2") (pintype "passive"))
      (node (ref "X2") (pin "1") (pinfunction "KL_1") (pintype "passive"))
    )
    (net (code "84") (name "unconnected-(IC1-AREF-Pad32)") (class "Default")
      (node (ref "IC1") (pin "32") (pinfunction "AREF_32") (pintype "passive"))
    )
    (net (code "85") (name "unconnected-(IC2-AREF-Pad21)") (class "Default")
      (node (ref "IC2") (pin "21") (pinfunction "AREF_21") (pintype "passive"))
    )
    (net (code "86") (name "unconnected-(IC2-PB0(ICP1{slash}CLKO{slash}PCINT0)-Pad14)") (class "Default")
      (node (ref "IC2") (pin "14") (pinfunction "PB0(ICP1/CLKO/PCINT0)_14") (pintype "bidirectional"))
    )
    (net (code "87") (name "unconnected-(IC2-PC3(ADC3{slash}PCINT11)-Pad26)") (class "Default")
      (node (ref "IC2") (pin "26") (pinfunction "PC3(ADC3/PCINT11)_26") (pintype "bidirectional"))
    )
    (net (code "88") (name "unconnected-(IC2-PC4(ADC4{slash}SDA{slash}PCINT12)-Pad27)") (class "Default")
      (node (ref "IC2") (pin "27") (pinfunction "PC4(ADC4/SDA/PCINT12)_27") (pintype "bidirectional"))
    )
    (net (code "89") (name "unconnected-(IC2-PC5(ADC5{slash}SCLPCINT13)-Pad28)") (class "Default")
      (node (ref "IC2") (pin "28") (pinfunction "PC5(ADC5/SCLPCINT13)_28") (pintype "bidirectional"))
    )
    (net (code "90") (name "unconnected-(K1B-O-PadO1)") (class "Default")
      (node (ref "K1") (pin "O1") (pinfunction "O_O1") (pintype "passive"))
    )
    (net (code "91") (name "unconnected-(K1C-O-PadO2)") (class "Default")
      (node (ref "K1") (pin "O2") (pinfunction "O_O2") (pintype "passive"))
    )
    (net (code "92") (name "unconnected-(OK1-VB-Pad7)") (class "Default")
      (node (ref "OK1") (pin "7") (pinfunction "VB_7") (pintype "passive"))
    )
    (net (code "93") (name "unconnected-(OK2-VB-Pad7)") (class "Default")
      (node (ref "OK2") (pin "7") (pinfunction "VB_7") (pintype "passive"))
    )
    (net (code "94") (name "unconnected-(OK3-VB-Pad7)") (class "Default")
      (node (ref "OK3") (pin "7") (pinfunction "VB_7") (pintype "passive"))
    )
    (net (code "95") (name "unconnected-(OK4-VB-Pad7)") (class "Default")
      (node (ref "OK4") (pin "7") (pinfunction "VB_7") (pintype "passive"))
    )
    (net (code "96") (name "unconnected-(OK5-VB-Pad7)") (class "Default")
      (node (ref "OK5") (pin "7") (pinfunction "VB_7") (pintype "passive"))
    )
    (net (code "97") (name "unconnected-(OK6-VB-Pad7)") (class "Default")
      (node (ref "OK6") (pin "7") (pinfunction "VB_7") (pintype "passive"))
    )
    (net (code "98") (name "unconnected-(R18-PadA)") (class "Default")
      (node (ref "R18") (pin "A") (pinfunction "A_A") (pintype "passive"))
    )
    (net (code "99") (name "unconnected-(SV4-Pad2)") (class "Default")
      (node (ref "SV4") (pin "2") (pinfunction "2_2") (pintype "passive"))
    )
    (net (code "100") (name "unconnected-(SV4-Pad8)") (class "Default")
      (node (ref "SV4") (pin "8") (pinfunction "8_8") (pintype "passive"))
    )
    (net (code "101") (name "unconnected-(SV4-Pad12)") (class "Default")
      (node (ref "SV4") (pin "12") (pinfunction "12_12") (pintype "passive"))
    )
    (net (code "102") (name "unconnected-(SV4-Pad14)") (class "Default")
      (node (ref "SV4") (pin "14") (pinfunction "14_14") (pintype "passive"))
    )
  )
)
